# Digital_DSP.net
KiCad netlist of a schematic drawn in Altium Designer
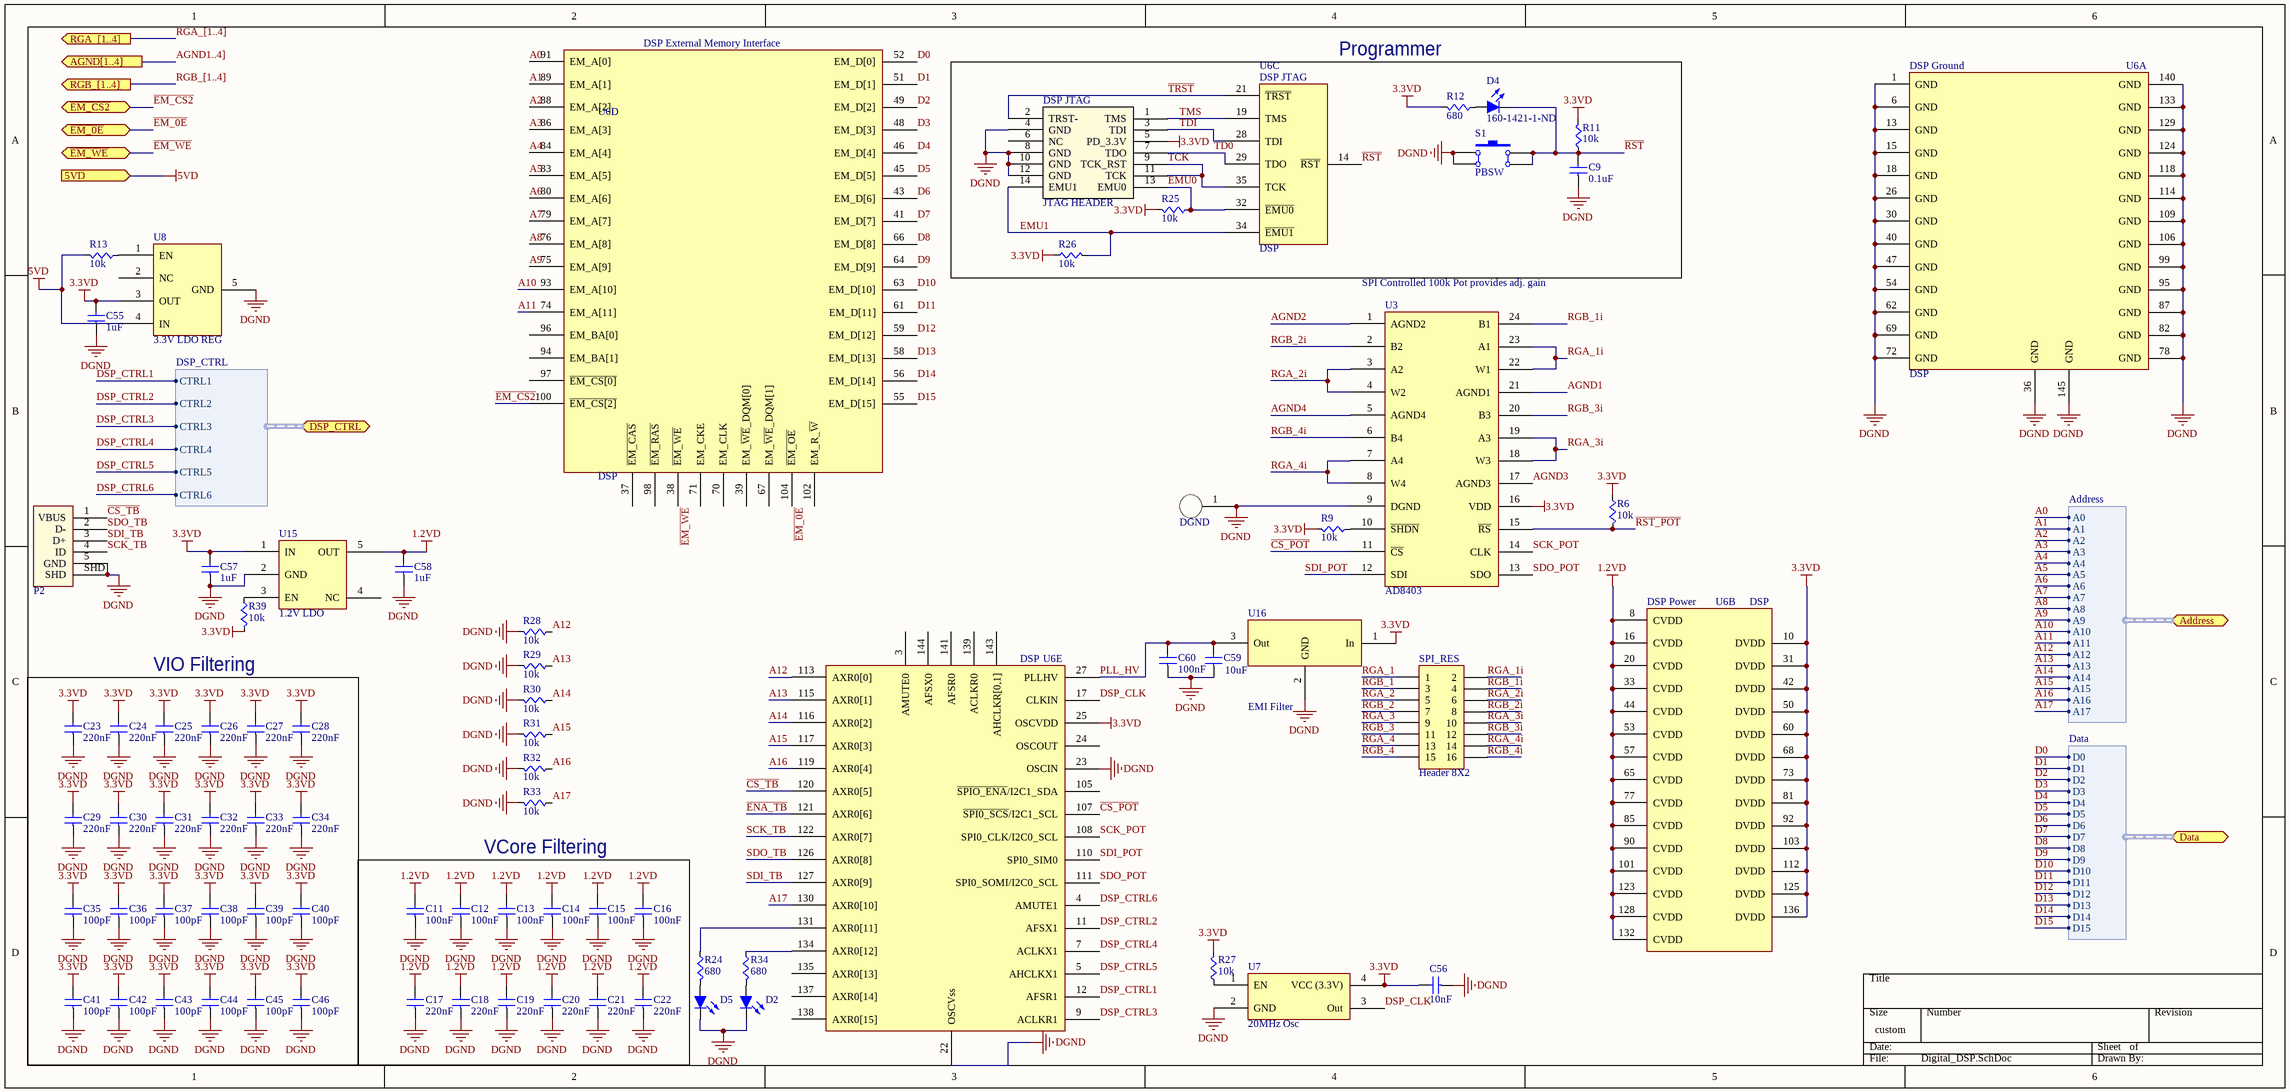
[diagram p0: Digital_DSP.SchDoc]

(export (version "E")
  (design (tool "Eeschema 10.0.6"))
  (components
    (comp (ref "C9")
      (value "0.1uF")
      (footprint "CAPC0603")
      (fields (field (name "Comment") "Cap"))
      (libsource (lib "SubjuGator8") (part "Cap"))
    )
    (comp (ref "C11")
      (value "100nF")
      (footprint "CAPC0603")
      (fields (field (name "Comment") "Cap"))
      (libsource (lib "SubjuGator8") (part "Cap"))
    )
    (comp (ref "C12")
      (value "100nF")
      (footprint "CAPC0603")
      (fields (field (name "Comment") "Cap"))
      (libsource (lib "SubjuGator8") (part "Cap"))
    )
    (comp (ref "C13")
      (value "100nF")
      (footprint "CAPC0603")
      (fields (field (name "Comment") "Cap"))
      (libsource (lib "SubjuGator8") (part "Cap"))
    )
    (comp (ref "C14")
      (value "100nF")
      (footprint "CAPC0603")
      (fields (field (name "Comment") "Cap"))
      (libsource (lib "SubjuGator8") (part "Cap"))
    )
    (comp (ref "C15")
      (value "100nF")
      (footprint "CAPC0603")
      (fields (field (name "Comment") "Cap"))
      (libsource (lib "SubjuGator8") (part "Cap"))
    )
    (comp (ref "C16")
      (value "100nF")
      (footprint "CAPC0603")
      (fields (field (name "Comment") "Cap"))
      (libsource (lib "SubjuGator8") (part "Cap"))
    )
    (comp (ref "C17")
      (value "220nF")
      (footprint "CAPC0603")
      (fields (field (name "Comment") "Cap"))
      (libsource (lib "SubjuGator8") (part "Cap"))
    )
    (comp (ref "C18")
      (value "220nF")
      (footprint "CAPC0603")
      (fields (field (name "Comment") "Cap"))
      (libsource (lib "SubjuGator8") (part "Cap"))
    )
    (comp (ref "C19")
      (value "220nF")
      (footprint "CAPC0603")
      (fields (field (name "Comment") "Cap"))
      (libsource (lib "SubjuGator8") (part "Cap"))
    )
    (comp (ref "C20")
      (value "220nF")
      (footprint "CAPC0603")
      (fields (field (name "Comment") "Cap"))
      (libsource (lib "SubjuGator8") (part "Cap"))
    )
    (comp (ref "C21")
      (value "220nF")
      (footprint "CAPC0603")
      (fields (field (name "Comment") "Cap"))
      (libsource (lib "SubjuGator8") (part "Cap"))
    )
    (comp (ref "C22")
      (value "220nF")
      (footprint "CAPC0603")
      (fields (field (name "Comment") "Cap"))
      (libsource (lib "SubjuGator8") (part "Cap"))
    )
    (comp (ref "C23")
      (value "220nF")
      (footprint "CAPC0603")
      (fields (field (name "Comment") "Cap"))
      (libsource (lib "SubjuGator8") (part "Cap"))
    )
    (comp (ref "C24")
      (value "220nF")
      (footprint "CAPC0603")
      (fields (field (name "Comment") "Cap"))
      (libsource (lib "SubjuGator8") (part "Cap"))
    )
    (comp (ref "C25")
      (value "220nF")
      (footprint "CAPC0603")
      (fields (field (name "Comment") "Cap"))
      (libsource (lib "SubjuGator8") (part "Cap"))
    )
    (comp (ref "C26")
      (value "220nF")
      (footprint "CAPC0603")
      (fields (field (name "Comment") "Cap"))
      (libsource (lib "SubjuGator8") (part "Cap"))
    )
    (comp (ref "C27")
      (value "220nF")
      (footprint "CAPC0603")
      (fields (field (name "Comment") "Cap"))
      (libsource (lib "SubjuGator8") (part "Cap"))
    )
    (comp (ref "C28")
      (value "220nF")
      (footprint "CAPC0603")
      (fields (field (name "Comment") "Cap"))
      (libsource (lib "SubjuGator8") (part "Cap"))
    )
    (comp (ref "C29")
      (value "220nF")
      (footprint "CAPC0603")
      (fields (field (name "Comment") "Cap"))
      (libsource (lib "SubjuGator8") (part "Cap"))
    )
    (comp (ref "C30")
      (value "220nF")
      (footprint "CAPC0603")
      (fields (field (name "Comment") "Cap"))
      (libsource (lib "SubjuGator8") (part "Cap"))
    )
    (comp (ref "C31")
      (value "220nF")
      (footprint "CAPC0603")
      (fields (field (name "Comment") "Cap"))
      (libsource (lib "SubjuGator8") (part "Cap"))
    )
    (comp (ref "C32")
      (value "220nF")
      (footprint "CAPC0603")
      (fields (field (name "Comment") "Cap"))
      (libsource (lib "SubjuGator8") (part "Cap"))
    )
    (comp (ref "C33")
      (value "220nF")
      (footprint "CAPC0603")
      (fields (field (name "Comment") "Cap"))
      (libsource (lib "SubjuGator8") (part "Cap"))
    )
    (comp (ref "C34")
      (value "220nF")
      (footprint "CAPC0603")
      (fields (field (name "Comment") "Cap"))
      (libsource (lib "SubjuGator8") (part "Cap"))
    )
    (comp (ref "C35")
      (value "100pF")
      (footprint "CAPC0603")
      (fields (field (name "Comment") "Cap"))
      (libsource (lib "SubjuGator8") (part "Cap"))
    )
    (comp (ref "C36")
      (value "100pF")
      (footprint "CAPC0603")
      (fields (field (name "Comment") "Cap"))
      (libsource (lib "SubjuGator8") (part "Cap"))
    )
    (comp (ref "C37")
      (value "100pF")
      (footprint "CAPC0603")
      (fields (field (name "Comment") "Cap"))
      (libsource (lib "SubjuGator8") (part "Cap"))
    )
    (comp (ref "C38")
      (value "100pF")
      (footprint "CAPC0603")
      (fields (field (name "Comment") "Cap"))
      (libsource (lib "SubjuGator8") (part "Cap"))
    )
    (comp (ref "C39")
      (value "100pF")
      (footprint "CAPC0603")
      (fields (field (name "Comment") "Cap"))
      (libsource (lib "SubjuGator8") (part "Cap"))
    )
    (comp (ref "C40")
      (value "100pF")
      (footprint "CAPC0603")
      (fields (field (name "Comment") "Cap"))
      (libsource (lib "SubjuGator8") (part "Cap"))
    )
    (comp (ref "C41")
      (value "100pF")
      (footprint "CAPC0603")
      (fields (field (name "Comment") "Cap"))
      (libsource (lib "SubjuGator8") (part "Cap"))
    )
    (comp (ref "C42")
      (value "100pF")
      (footprint "CAPC0603")
      (fields (field (name "Comment") "Cap"))
      (libsource (lib "SubjuGator8") (part "Cap"))
    )
    (comp (ref "C43")
      (value "100pF")
      (footprint "CAPC0603")
      (fields (field (name "Comment") "Cap"))
      (libsource (lib "SubjuGator8") (part "Cap"))
    )
    (comp (ref "C44")
      (value "100pF")
      (footprint "CAPC0603")
      (fields (field (name "Comment") "Cap"))
      (libsource (lib "SubjuGator8") (part "Cap"))
    )
    (comp (ref "C45")
      (value "100pF")
      (footprint "CAPC0603")
      (fields (field (name "Comment") "Cap"))
      (libsource (lib "SubjuGator8") (part "Cap"))
    )
    (comp (ref "C46")
      (value "100pF")
      (footprint "CAPC0603")
      (fields (field (name "Comment") "Cap"))
      (libsource (lib "SubjuGator8") (part "Cap"))
    )
    (comp (ref "C55")
      (value "1uF")
      (footprint "CAPC0603")
      (description "CAP CER 1UF 50V 10% X7R 1206")
      (fields (field (name "Comment") "Cap1206"))
      (libsource (lib "Passives") (part "Cap1206"))
    )
    (comp (ref "C56")
      (value "10nF")
      (footprint "CAPC0603")
      (fields (field (name "Comment") "Cap"))
      (libsource (lib "SubjuGator8") (part "Cap"))
    )
    (comp (ref "C57")
      (value "1uF")
      (footprint "CAPC0603")
      (description "CAP CER 1UF 50V 10% X7R 1206")
      (fields (field (name "Comment") "Cap1206"))
      (libsource (lib "Passives") (part "Cap1206"))
    )
    (comp (ref "C58")
      (value "1uF")
      (footprint "CAPC0603")
      (description "CAP CER 1UF 50V 10% X7R 1206")
      (fields (field (name "Comment") "Cap1206"))
      (libsource (lib "Passives") (part "Cap1206"))
    )
    (comp (ref "C59")
      (value "10uF")
      (footprint "CAP1210")
      (description "CAP CER 10UF 50V 20% X5R 1210")
      (fields (field (name "Comment") "CAP1210"))
      (libsource (lib "SubjuGator8") (part "CAP1210"))
    )
    (comp (ref "C60")
      (value "100nF")
      (footprint "CAPC0603")
      (fields (field (name "Comment") "Cap"))
      (libsource (lib "SubjuGator8") (part "Cap"))
    )
    (comp (ref "D2")
      (value "LED-RED")
      (footprint "Hydrophone:LED0805-RED")
      (description "Light Emitting Diode - RED")
      (fields
        (field (name "MANUFACTURER PART NUMBER") "LTST-C171CKT")
        (field (name "MANUFACTURER") "Lite-On Inc")
      )
      (libsource (lib "Hydrophone") (part "LED-RED"))
    )
    (comp (ref "D4")
      (value "LED-RED")
      (footprint "Hydrophone:LED0805-RED")
      (description "Light Emitting Diode - RED")
      (fields
        (field (name "MANUFACTURER PART NUMBER") "LTST-C171CKT")
        (field (name "MANUFACTURER") "Lite-On Inc")
        (field (name "SUPPLIER PART NUMBER") "160-1421-1-ND")
      )
      (libsource (lib "Hydrophone") (part "LED-RED"))
    )
    (comp (ref "D5")
      (value "LED-RED")
      (footprint "Hydrophone:LED0805-RED")
      (description "Light Emitting Diode - RED")
      (fields
        (field (name "MANUFACTURER PART NUMBER") "LTST-C171CKT")
        (field (name "MANUFACTURER") "Lite-On Inc")
      )
      (libsource (lib "Hydrophone") (part "LED-RED"))
    )
    (comp (ref "DGND")
      (value "Test_Point")
      (footprint "TP")
      (description "TEST POINT PC COMPACT .063\"D")
      (libsource (lib "Hydrophone") (part "Test_Point"))
    )
    (comp (ref "DSP JTAG")
      (value "JTAG HEADER")
      (footprint "Hydrophone:JTAG HEADER - 14")
      (description "14 Pin JTAG Header")
      (libsource (lib "Hydrophone") (part "JTAG-TI_14"))
    )
    (comp (ref "P2")
      (value "USB Micro")
      (footprint "10118192-0001LF")
      (description "USB Mini B Metal Shield SMT")
      (libsource (lib "SubjuGator8") (part "USB Micro"))
    )
    (comp (ref "R6")
      (value "10k")
      (footprint "RES0603")
      (fields (field (name "Comment") "Res"))
      (libsource (lib "SubjuGator8") (part "Res"))
    )
    (comp (ref "R9")
      (value "10k")
      (footprint "RES0603")
      (fields (field (name "Comment") "Res"))
      (libsource (lib "SubjuGator8") (part "Res"))
    )
    (comp (ref "R11")
      (value "10k")
      (footprint "RES0603")
      (fields (field (name "Comment") "Res"))
      (libsource (lib "Passives") (part "Res"))
    )
    (comp (ref "R12")
      (value "680")
      (footprint "RES0603")
      (fields (field (name "Comment") "Res"))
      (libsource (lib "SubjuGator8") (part "Res"))
    )
    (comp (ref "R13")
      (value "10k")
      (footprint "RES0603")
      (fields (field (name "Comment") "Res"))
      (libsource (lib "SubjuGator8") (part "Res"))
    )
    (comp (ref "R24")
      (value "680")
      (footprint "RES0603")
      (fields (field (name "Comment") "Res"))
      (libsource (lib "SubjuGator8") (part "Res"))
    )
    (comp (ref "R25")
      (value "10k")
      (footprint "RES0603")
      (fields (field (name "Comment") "Res"))
      (libsource (lib "SubjuGator8") (part "Res"))
    )
    (comp (ref "R26")
      (value "10k")
      (footprint "RES0603")
      (fields (field (name "Comment") "Res"))
      (libsource (lib "SubjuGator8") (part "Res"))
    )
    (comp (ref "R27")
      (value "10k")
      (footprint "RES0603")
      (fields (field (name "Comment") "Res"))
      (libsource (lib "SubjuGator8") (part "Res"))
    )
    (comp (ref "R28")
      (value "10k")
      (footprint "RES0603")
      (fields (field (name "Comment") "Res"))
      (libsource (lib "SubjuGator8") (part "Res"))
    )
    (comp (ref "R29")
      (value "10k")
      (footprint "RES0603")
      (fields (field (name "Comment") "Res"))
      (libsource (lib "SubjuGator8") (part "Res"))
    )
    (comp (ref "R30")
      (value "10k")
      (footprint "RES0603")
      (fields (field (name "Comment") "Res"))
      (libsource (lib "SubjuGator8") (part "Res"))
    )
    (comp (ref "R31")
      (value "10k")
      (footprint "RES0603")
      (fields (field (name "Comment") "Res"))
      (libsource (lib "SubjuGator8") (part "Res"))
    )
    (comp (ref "R32")
      (value "10k")
      (footprint "RES0603")
      (fields (field (name "Comment") "Res"))
      (libsource (lib "SubjuGator8") (part "Res"))
    )
    (comp (ref "R33")
      (value "10k")
      (footprint "RES0603")
      (fields (field (name "Comment") "Res"))
      (libsource (lib "SubjuGator8") (part "Res"))
    )
    (comp (ref "R34")
      (value "680")
      (footprint "RES0603")
      (fields (field (name "Comment") "Res"))
      (libsource (lib "SubjuGator8") (part "Res"))
    )
    (comp (ref "R39")
      (value "10k")
      (footprint "RES0603")
      (fields (field (name "Comment") "Res"))
      (libsource (lib "SubjuGator8") (part "Res"))
    )
    (comp (ref "S1")
      (value "PBSW")
      (footprint "Hydrophone:PBSW")
      (description "Push Button Switch")
      (fields
        (field (name "MANUFACTURER") "Panasonic Electronic Components")
        (field (name "MANUFACTURER PART NUMBER") "EVQ-9P105M")
        (field (name "PUBLISHER") "Altium Limited")
      )
      (libsource (lib "Hydrophone") (part "SW-PB"))
    )
    (comp (ref "SPI_RES")
      (value "Header 8X2")
      (footprint "HDR2X8")
      (description "Header, 8-Pin, Dual row")
      (fields (field (name "PUBLISHER") "Altium Limited"))
      (libsource (lib "Miscellaneous Connectors") (part "Header 8X2"))
    )
    (comp (ref "U3")
      (value "AD8403")
      (footprint "SOIC-24n")
      (description "IC POT DGTL 8BIT 100K 4CH 24SOIC")
      (libsource (lib "SubjuGator8") (part "AD8403"))
    )
    (comp (ref "U6")
      (value "DSP")
      (footprint "LQFP_EP-144")
      (description "IC FLOATING POINT DSP 144-HTQFP")
      (libsource (lib "ICs") (part "TMS320C6726B"))
    )
    (comp (ref "U7")
      (value "20MHz Osc")
      (footprint "4-SMD")
      (description "OSC XO 20.000MHZ HCMOS TTL SMD")
      (libsource (lib "SubjuGator8") (part "CB3LV-3C-20M0000"))
    )
    (comp (ref "U8")
      (value "3.3V LDO REG")
      (footprint "SOT223-8N")
      (description "IC REG LDO 3.3V 0.5A SOT223-5")
      (libsource (lib "SubjuGator8") (part "LP38691"))
    )
    (comp (ref "U15")
      (value "1.2V LDO")
      (footprint "sot23-5n")
      (description "IC REG LDO 1.2V 0.15A SOT23-5")
      (libsource (lib "SubjuGator8") (part "LP3990MF-1.2"))
    )
    (comp (ref "U16")
      (value "EMI Filter")
      (footprint "1812")
      (description "FILTER 3-TERM 12MHZ 300MA SMD")
      (libsource (lib "SubjuGator8") (part "ACF451832-333"))
    )
  )
  (nets
    (net (code "5") (name "/A0") (class "Default")
      (node (ref "U6") (pin "91") (pinfunction "EM_A[0]_91") (pintype "passive"))
    )
    (net (code "6") (name "/A1") (class "Default")
      (node (ref "U6") (pin "89") (pinfunction "EM_A[1]_89") (pintype "passive"))
    )
    (net (code "7") (name "/A2") (class "Default")
      (node (ref "U6") (pin "88") (pinfunction "EM_A[2]_88") (pintype "passive"))
    )
    (net (code "8") (name "/A3") (class "Default")
      (node (ref "U6") (pin "86") (pinfunction "EM_A[3]_86") (pintype "passive"))
    )
    (net (code "9") (name "/A4") (class "Default")
      (node (ref "U6") (pin "84") (pinfunction "EM_A[4]_84") (pintype "passive"))
    )
    (net (code "10") (name "/A5") (class "Default")
      (node (ref "U6") (pin "83") (pinfunction "EM_A[5]_83") (pintype "passive"))
    )
    (net (code "11") (name "/A6") (class "Default")
      (node (ref "U6") (pin "80") (pinfunction "EM_A[6]_80") (pintype "passive"))
    )
    (net (code "12") (name "/A7") (class "Default")
      (node (ref "U6") (pin "79") (pinfunction "EM_A[7]_79") (pintype "passive"))
    )
    (net (code "13") (name "/A8") (class "Default")
      (node (ref "U6") (pin "76") (pinfunction "EM_A[8]_76") (pintype "passive"))
    )
    (net (code "14") (name "/A9") (class "Default")
      (node (ref "U6") (pin "75") (pinfunction "EM_A[9]_75") (pintype "passive"))
    )
    (net (code "15") (name "/A10") (class "Default")
      (node (ref "U6") (pin "93") (pinfunction "EM_A[10]_93") (pintype "passive"))
    )
    (net (code "16") (name "/A11") (class "Default")
      (node (ref "U6") (pin "74") (pinfunction "EM_A[11]_74") (pintype "passive"))
    )
    (net (code "17") (name "/A12") (class "Default")
      (node (ref "R28") (pin "2") (pinfunction "B_2") (pintype "passive"))
      (node (ref "U6") (pin "113") (pinfunction "AXR0[0]_113") (pintype "passive"))
    )
    (net (code "18") (name "/A13") (class "Default")
      (node (ref "R29") (pin "2") (pinfunction "B_2") (pintype "passive"))
      (node (ref "U6") (pin "115") (pinfunction "AXR0[1]_115") (pintype "passive"))
    )
    (net (code "19") (name "/A14") (class "Default")
      (node (ref "R30") (pin "2") (pinfunction "B_2") (pintype "passive"))
      (node (ref "U6") (pin "116") (pinfunction "AXR0[2]_116") (pintype "passive"))
    )
    (net (code "20") (name "/A15") (class "Default")
      (node (ref "R31") (pin "2") (pinfunction "B_2") (pintype "passive"))
      (node (ref "U6") (pin "117") (pinfunction "AXR0[3]_117") (pintype "passive"))
    )
    (net (code "21") (name "/A16") (class "Default")
      (node (ref "R32") (pin "2") (pinfunction "B_2") (pintype "passive"))
      (node (ref "U6") (pin "119") (pinfunction "AXR0[4]_119") (pintype "passive"))
    )
    (net (code "22") (name "/A17") (class "Default")
      (node (ref "R33") (pin "2") (pinfunction "B_2") (pintype "passive"))
      (node (ref "U6") (pin "130") (pinfunction "AXR0[10]_130") (pintype "passive"))
    )
    (net (code "23") (name "/AGND1") (class "Default")
      (node (ref "U3") (pin "21") (pinfunction "AGND1_21") (pintype "passive"))
    )
    (net (code "24") (name "/AGND2") (class "Default")
      (node (ref "U3") (pin "1") (pinfunction "AGND2_1") (pintype "passive"))
    )
    (net (code "25") (name "/AGND3") (class "Default")
      (node (ref "U3") (pin "17") (pinfunction "AGND3_17") (pintype "passive"))
    )
    (net (code "26") (name "/AGND4") (class "Default")
      (node (ref "U3") (pin "5") (pinfunction "AGND4_5") (pintype "passive"))
    )
    (net (code "27") (name "/D0") (class "Default")
      (node (ref "U6") (pin "52") (pinfunction "EM_D[0]_52") (pintype "passive"))
    )
    (net (code "28") (name "/D1") (class "Default")
      (node (ref "U6") (pin "51") (pinfunction "EM_D[1]_51") (pintype "passive"))
    )
    (net (code "29") (name "/D2") (class "Default")
      (node (ref "U6") (pin "49") (pinfunction "EM_D[2]_49") (pintype "passive"))
    )
    (net (code "30") (name "/D3") (class "Default")
      (node (ref "U6") (pin "48") (pinfunction "EM_D[3]_48") (pintype "passive"))
    )
    (net (code "31") (name "/D4") (class "Default")
      (node (ref "U6") (pin "46") (pinfunction "EM_D[4]_46") (pintype "passive"))
    )
    (net (code "32") (name "/D5") (class "Default")
      (node (ref "U6") (pin "45") (pinfunction "EM_D[5]_45") (pintype "passive"))
    )
    (net (code "33") (name "/D6") (class "Default")
      (node (ref "U6") (pin "43") (pinfunction "EM_D[6]_43") (pintype "passive"))
    )
    (net (code "34") (name "/D7") (class "Default")
      (node (ref "U6") (pin "41") (pinfunction "EM_D[7]_41") (pintype "passive"))
    )
    (net (code "35") (name "/D8") (class "Default")
      (node (ref "U6") (pin "66") (pinfunction "EM_D[8]_66") (pintype "passive"))
    )
    (net (code "36") (name "/D9") (class "Default")
      (node (ref "U6") (pin "64") (pinfunction "EM_D[9]_64") (pintype "passive"))
    )
    (net (code "37") (name "/D10") (class "Default")
      (node (ref "U6") (pin "63") (pinfunction "EM_D[10]_63") (pintype "passive"))
    )
    (net (code "38") (name "/D11") (class "Default")
      (node (ref "U6") (pin "61") (pinfunction "EM_D[11]_61") (pintype "passive"))
    )
    (net (code "39") (name "/D12") (class "Default")
      (node (ref "U6") (pin "59") (pinfunction "EM_D[12]_59") (pintype "passive"))
    )
    (net (code "40") (name "/D13") (class "Default")
      (node (ref "U6") (pin "58") (pinfunction "EM_D[13]_58") (pintype "passive"))
    )
    (net (code "41") (name "/D14") (class "Default")
      (node (ref "U6") (pin "56") (pinfunction "EM_D[14]_56") (pintype "passive"))
    )
    (net (code "42") (name "/D15") (class "Default")
      (node (ref "U6") (pin "55") (pinfunction "EM_D[15]_55") (pintype "passive"))
    )
    (net (code "43") (name "/DSP_CLK") (class "Default")
      (node (ref "U6") (pin "17") (pinfunction "CLKIN_17") (pintype "passive"))
      (node (ref "U7") (pin "3") (pinfunction "Out_3") (pintype "passive"))
    )
    (net (code "44") (name "/DSP_CTRL1") (class "Default")
      (node (ref "U6") (pin "12") (pinfunction "AFSR1_12") (pintype "passive"))
    )
    (net (code "45") (name "/DSP_CTRL2") (class "Default")
      (node (ref "U6") (pin "11") (pinfunction "AFSX1_11") (pintype "passive"))
    )
    (net (code "46") (name "/DSP_CTRL3") (class "Default")
      (node (ref "U6") (pin "9") (pinfunction "ACLKR1_9") (pintype "passive"))
    )
    (net (code "47") (name "/DSP_CTRL4") (class "Default")
      (node (ref "U6") (pin "7") (pinfunction "ACLKX1_7") (pintype "passive"))
    )
    (net (code "48") (name "/DSP_CTRL5") (class "Default")
      (node (ref "U6") (pin "5") (pinfunction "AHCLKX1_5") (pintype "passive"))
    )
    (net (code "49") (name "/DSP_CTRL6") (class "Default")
      (node (ref "U6") (pin "4") (pinfunction "AMUTE1_4") (pintype "passive"))
    )
    (net (code "50") (name "/EMU0") (class "Default")
      (node (ref "DSP JTAG") (pin "13") (pinfunction "EMU0_13") (pintype "passive"))
      (node (ref "R25") (pin "2") (pinfunction "B_2") (pintype "passive"))
      (node (ref "U6") (pin "32") (pinfunction "~{EMU0}_32") (pintype "passive"))
    )
    (net (code "51") (name "/EMU1") (class "Default")
      (node (ref "DSP JTAG") (pin "14") (pinfunction "EMU1_14") (pintype "passive"))
      (node (ref "R26") (pin "1") (pinfunction "A_1") (pintype "passive"))
      (node (ref "U6") (pin "34") (pinfunction "~{EMU1}_34") (pintype "passive"))
    )
    (net (code "52") (name "/PLL_HV") (class "Default")
      (node (ref "C59") (pin "1") (pinfunction "A_1") (pintype "passive"))
      (node (ref "C60") (pin "1") (pinfunction "A_1") (pintype "passive"))
      (node (ref "U16") (pin "3") (pinfunction "Out_3") (pintype "passive"))
      (node (ref "U6") (pin "27") (pinfunction "PLLHV_27") (pintype "passive"))
    )
    (net (code "53") (name "/RGA_1") (class "Default")
      (node (ref "SPI_RES") (pin "1") (pinfunction "1_1") (pintype "passive"))
    )
    (net (code "54") (name "/RGA_1i") (class "Default")
      (node (ref "SPI_RES") (pin "2") (pinfunction "2_2") (pintype "passive"))
      (node (ref "U3") (pin "22") (pinfunction "W1_22") (pintype "passive"))
      (node (ref "U3") (pin "23") (pinfunction "A1_23") (pintype "passive"))
    )
    (net (code "55") (name "/RGA_2") (class "Default")
      (node (ref "SPI_RES") (pin "5") (pinfunction "5_5") (pintype "passive"))
    )
    (net (code "56") (name "/RGA_2i") (class "Default")
      (node (ref "SPI_RES") (pin "6") (pinfunction "6_6") (pintype "passive"))
      (node (ref "U3") (pin "3") (pinfunction "A2_3") (pintype "passive"))
      (node (ref "U3") (pin "4") (pinfunction "W2_4") (pintype "passive"))
    )
    (net (code "57") (name "/RGA_3") (class "Default")
      (node (ref "SPI_RES") (pin "9") (pinfunction "9_9") (pintype "passive"))
    )
    (net (code "58") (name "/RGA_3i") (class "Default")
      (node (ref "SPI_RES") (pin "10") (pinfunction "10_10") (pintype "passive"))
      (node (ref "U3") (pin "18") (pinfunction "W3_18") (pintype "passive"))
      (node (ref "U3") (pin "19") (pinfunction "A3_19") (pintype "passive"))
    )
    (net (code "59") (name "/RGA_4") (class "Default")
      (node (ref "SPI_RES") (pin "13") (pinfunction "13_13") (pintype "passive"))
    )
    (net (code "60") (name "/RGA_4i") (class "Default")
      (node (ref "SPI_RES") (pin "14") (pinfunction "14_14") (pintype "passive"))
      (node (ref "U3") (pin "7") (pinfunction "A4_7") (pintype "passive"))
      (node (ref "U3") (pin "8") (pinfunction "W4_8") (pintype "passive"))
    )
    (net (code "62") (name "/RGB_1") (class "Default")
      (node (ref "SPI_RES") (pin "3") (pinfunction "3_3") (pintype "passive"))
    )
    (net (code "63") (name "/RGB_1i") (class "Default")
      (node (ref "SPI_RES") (pin "4") (pinfunction "4_4") (pintype "passive"))
      (node (ref "U3") (pin "24") (pinfunction "B1_24") (pintype "passive"))
    )
    (net (code "64") (name "/RGB_2") (class "Default")
      (node (ref "SPI_RES") (pin "7") (pinfunction "7_7") (pintype "passive"))
    )
    (net (code "65") (name "/RGB_2i") (class "Default")
      (node (ref "SPI_RES") (pin "8") (pinfunction "8_8") (pintype "passive"))
      (node (ref "U3") (pin "2") (pinfunction "B2_2") (pintype "passive"))
    )
    (net (code "66") (name "/RGB_3") (class "Default")
      (node (ref "SPI_RES") (pin "11") (pinfunction "11_11") (pintype "passive"))
    )
    (net (code "67") (name "/RGB_3i") (class "Default")
      (node (ref "SPI_RES") (pin "12") (pinfunction "12_12") (pintype "passive"))
      (node (ref "U3") (pin "20") (pinfunction "B3_20") (pintype "passive"))
    )
    (net (code "68") (name "/RGB_4") (class "Default")
      (node (ref "SPI_RES") (pin "15") (pinfunction "15_15") (pintype "passive"))
    )
    (net (code "69") (name "/RGB_4i") (class "Default")
      (node (ref "SPI_RES") (pin "16") (pinfunction "16_16") (pintype "passive"))
      (node (ref "U3") (pin "6") (pinfunction "B4_6") (pintype "passive"))
    )
    (net (code "71") (name "/SCK_POT") (class "Default")
      (node (ref "U3") (pin "14") (pinfunction "CLK_14") (pintype "passive"))
      (node (ref "U6") (pin "108") (pinfunction "SPI0_CLK/I2C0_SCL_108") (pintype "passive"))
    )
    (net (code "72") (name "/SCK_TB") (class "Default")
      (node (ref "P2") (pin "4") (pinfunction "ID_4") (pintype "passive"))
      (node (ref "U6") (pin "122") (pinfunction "AXR0[7]_122") (pintype "passive"))
    )
    (net (code "73") (name "/SDI_POT") (class "Default")
      (node (ref "U3") (pin "12") (pinfunction "SDI_12") (pintype "passive"))
      (node (ref "U6") (pin "110") (pinfunction "SPI0_SIM0_110") (pintype "passive"))
    )
    (net (code "74") (name "/SDI_TB") (class "Default")
      (node (ref "P2") (pin "3") (pinfunction "D+_3") (pintype "passive"))
      (node (ref "U6") (pin "127") (pinfunction "AXR0[9]_127") (pintype "passive"))
    )
    (net (code "75") (name "/SDO_POT") (class "Default")
      (node (ref "U3") (pin "13") (pinfunction "SDO_13") (pintype "passive"))
      (node (ref "U6") (pin "111") (pinfunction "SPI0_SOMI/I2C0_SCL_111") (pintype "passive"))
    )
    (net (code "76") (name "/SDO_TB") (class "Default")
      (node (ref "P2") (pin "2") (pinfunction "D-_2") (pintype "passive"))
      (node (ref "U6") (pin "126") (pinfunction "AXR0[8]_126") (pintype "passive"))
    )
    (net (code "77") (name "/TCK") (class "Default")
      (node (ref "DSP JTAG") (pin "11") (pinfunction "TCK_11") (pintype "passive"))
      (node (ref "DSP JTAG") (pin "9") (pinfunction "TCK_RST_9") (pintype "passive"))
      (node (ref "U6") (pin "35") (pinfunction "TCK_35") (pintype "passive"))
    )
    (net (code "78") (name "/TD0") (class "Default")
      (node (ref "DSP JTAG") (pin "7") (pinfunction "TDO_7") (pintype "passive"))
      (node (ref "U6") (pin "29") (pinfunction "TDO_29") (pintype "passive"))
    )
    (net (code "79") (name "/TDI") (class "Default")
      (node (ref "DSP JTAG") (pin "3") (pinfunction "TDI_3") (pintype "passive"))
      (node (ref "U6") (pin "28") (pinfunction "TDI_28") (pintype "passive"))
    )
    (net (code "80") (name "/TMS") (class "Default")
      (node (ref "DSP JTAG") (pin "1") (pinfunction "TMS_1") (pintype "passive"))
      (node (ref "U6") (pin "19") (pinfunction "TMS_19") (pintype "passive"))
    )
    (net (code "85") (name "/~{CS_POT}") (class "Default")
      (node (ref "U3") (pin "11") (pinfunction "~{CS}_11") (pintype "passive"))
      (node (ref "U6") (pin "107") (pinfunction "~{SPI0_SCS}/I2C1_SCL_107") (pintype "passive"))
    )
    (net (code "86") (name "/~{CS_TB}") (class "Default")
      (node (ref "P2") (pin "1") (pinfunction "VBUS_1") (pintype "passive"))
      (node (ref "U6") (pin "120") (pinfunction "AXR0[5]_120") (pintype "passive"))
    )
    (net (code "87") (name "/~{EM_0E}") (class "Default")
      (node (ref "U6") (pin "104") (pinfunction "~{EM_OE}_104") (pintype "passive"))
    )
    (net (code "88") (name "/~{EM_CS2}") (class "Default")
      (node (ref "U6") (pin "100") (pinfunction "~{EM_CS[2]}_100") (pintype "passive"))
    )
    (net (code "89") (name "/~{EM_WE}") (class "Default")
      (node (ref "U6") (pin "38") (pinfunction "~{EM_WE}_38") (pintype "passive"))
    )
    (net (code "90") (name "/~{ENA_TB}") (class "Default")
      (node (ref "U6") (pin "121") (pinfunction "AXR0[6]_121") (pintype "passive"))
    )
    (net (code "91") (name "/~{RST_POT}") (class "Default")
      (node (ref "R6") (pin "1") (pinfunction "A_1") (pintype "passive"))
      (node (ref "U3") (pin "15") (pinfunction "~{RS}_15") (pintype "passive"))
    )
    (net (code "92") (name "/~{RST}") (class "Default")
      (node (ref "C9") (pin "1") (pinfunction "A_1") (pintype "passive"))
      (node (ref "D4") (pin "1") (pinfunction "K_1") (pintype "passive"))
      (node (ref "R11") (pin "2") (pinfunction "B_2") (pintype "passive"))
      (node (ref "S1") (pin "3") (pinfunction "B_3") (pintype "passive"))
      (node (ref "S1") (pin "4") (pinfunction "B'_4") (pintype "passive"))
      (node (ref "U6") (pin "14") (pinfunction "~{RST}_14") (pintype "passive"))
    )
    (net (code "93") (name "/~{TRST}") (class "Default")
      (node (ref "DSP JTAG") (pin "2") (pinfunction "TRST-_2") (pintype "passive"))
      (node (ref "U6") (pin "21") (pinfunction "~{TRST}_21") (pintype "passive"))
    )
    (net (code "94") (name "1.2VD") (class "Default")
      (node (ref "C11") (pin "1") (pinfunction "A_1") (pintype "passive"))
      (node (ref "C12") (pin "1") (pinfunction "A_1") (pintype "passive"))
      (node (ref "C13") (pin "1") (pinfunction "A_1") (pintype "passive"))
      (node (ref "C14") (pin "1") (pinfunction "A_1") (pintype "passive"))
      (node (ref "C15") (pin "1") (pinfunction "A_1") (pintype "passive"))
      (node (ref "C16") (pin "1") (pinfunction "A_1") (pintype "passive"))
      (node (ref "C17") (pin "1") (pinfunction "A_1") (pintype "passive"))
      (node (ref "C18") (pin "1") (pinfunction "A_1") (pintype "passive"))
      (node (ref "C19") (pin "1") (pinfunction "A_1") (pintype "passive"))
      (node (ref "C20") (pin "1") (pinfunction "A_1") (pintype "passive"))
      (node (ref "C21") (pin "1") (pinfunction "A_1") (pintype "passive"))
      (node (ref "C22") (pin "1") (pinfunction "A_1") (pintype "passive"))
      (node (ref "C58") (pin "1") (pinfunction "A_1") (pintype "passive"))
      (node (ref "U15") (pin "5") (pinfunction "OUT_5") (pintype "passive"))
      (node (ref "U6") (pin "101") (pinfunction "CVDD_101") (pintype "passive"))
      (node (ref "U6") (pin "123") (pinfunction "CVDD_123") (pintype "passive"))
      (node (ref "U6") (pin "128") (pinfunction "CVDD_128") (pintype "passive"))
      (node (ref "U6") (pin "132") (pinfunction "CVDD_132") (pintype "passive"))
      (node (ref "U6") (pin "16") (pinfunction "CVDD_16") (pintype "passive"))
      (node (ref "U6") (pin "20") (pinfunction "CVDD_20") (pintype "passive"))
      (node (ref "U6") (pin "33") (pinfunction "CVDD_33") (pintype "passive"))
      (node (ref "U6") (pin "44") (pinfunction "CVDD_44") (pintype "passive"))
      (node (ref "U6") (pin "53") (pinfunction "CVDD_53") (pintype "passive"))
      (node (ref "U6") (pin "57") (pinfunction "CVDD_57") (pintype "passive"))
      (node (ref "U6") (pin "65") (pinfunction "CVDD_65") (pintype "passive"))
      (node (ref "U6") (pin "77") (pinfunction "CVDD_77") (pintype "passive"))
      (node (ref "U6") (pin "8") (pinfunction "CVDD_8") (pintype "passive"))
      (node (ref "U6") (pin "85") (pinfunction "CVDD_85") (pintype "passive"))
      (node (ref "U6") (pin "90") (pinfunction "CVDD_90") (pintype "passive"))
    )
    (net (code "95") (name "3.3VD") (class "Default")
      (node (ref "C23") (pin "1") (pinfunction "A_1") (pintype "passive"))
      (node (ref "C24") (pin "1") (pinfunction "A_1") (pintype "passive"))
      (node (ref "C25") (pin "1") (pinfunction "A_1") (pintype "passive"))
      (node (ref "C26") (pin "1") (pinfunction "A_1") (pintype "passive"))
      (node (ref "C27") (pin "1") (pinfunction "A_1") (pintype "passive"))
      (node (ref "C28") (pin "1") (pinfunction "A_1") (pintype "passive"))
      (node (ref "C29") (pin "1") (pinfunction "A_1") (pintype "passive"))
      (node (ref "C30") (pin "1") (pinfunction "A_1") (pintype "passive"))
      (node (ref "C31") (pin "1") (pinfunction "A_1") (pintype "passive"))
      (node (ref "C32") (pin "1") (pinfunction "A_1") (pintype "passive"))
      (node (ref "C33") (pin "1") (pinfunction "A_1") (pintype "passive"))
      (node (ref "C34") (pin "1") (pinfunction "A_1") (pintype "passive"))
      (node (ref "C35") (pin "1") (pinfunction "A_1") (pintype "passive"))
      (node (ref "C36") (pin "1") (pinfunction "A_1") (pintype "passive"))
      (node (ref "C37") (pin "1") (pinfunction "A_1") (pintype "passive"))
      (node (ref "C38") (pin "1") (pinfunction "A_1") (pintype "passive"))
      (node (ref "C39") (pin "1") (pinfunction "A_1") (pintype "passive"))
      (node (ref "C40") (pin "1") (pinfunction "A_1") (pintype "passive"))
      (node (ref "C41") (pin "1") (pinfunction "A_1") (pintype "passive"))
      (node (ref "C42") (pin "1") (pinfunction "A_1") (pintype "passive"))
      (node (ref "C43") (pin "1") (pinfunction "A_1") (pintype "passive"))
      (node (ref "C44") (pin "1") (pinfunction "A_1") (pintype "passive"))
      (node (ref "C45") (pin "1") (pinfunction "A_1") (pintype "passive"))
      (node (ref "C46") (pin "1") (pinfunction "A_1") (pintype "passive"))
      (node (ref "C55") (pin "1") (pinfunction "A_1") (pintype "passive"))
      (node (ref "C56") (pin "1") (pinfunction "A_1") (pintype "passive"))
      (node (ref "C57") (pin "1") (pinfunction "A_1") (pintype "passive"))
      (node (ref "DSP JTAG") (pin "5") (pinfunction "PD_3.3V_5") (pintype "passive"))
      (node (ref "R11") (pin "1") (pinfunction "A_1") (pintype "passive"))
      (node (ref "R12") (pin "1") (pinfunction "A_1") (pintype "passive"))
      (node (ref "R25") (pin "1") (pinfunction "A_1") (pintype "passive"))
      (node (ref "R26") (pin "2") (pinfunction "B_2") (pintype "passive"))
      (node (ref "R27") (pin "1") (pinfunction "A_1") (pintype "passive"))
      (node (ref "R39") (pin "1") (pinfunction "A_1") (pintype "passive"))
      (node (ref "R6") (pin "2") (pinfunction "B_2") (pintype "passive"))
      (node (ref "R9") (pin "1") (pinfunction "A_1") (pintype "passive"))
      (node (ref "U15") (pin "1") (pinfunction "IN_1") (pintype "passive"))
      (node (ref "U16") (pin "1") (pinfunction "In_1") (pintype "passive"))
      (node (ref "U3") (pin "16") (pinfunction "VDD_16") (pintype "passive"))
      (node (ref "U6") (pin "10") (pinfunction "DVDD_10") (pintype "passive"))
      (node (ref "U6") (pin "103") (pinfunction "DVDD_103") (pintype "passive"))
      (node (ref "U6") (pin "112") (pinfunction "DVDD_112") (pintype "passive"))
      (node (ref "U6") (pin "125") (pinfunction "DVDD_125") (pintype "passive"))
      (node (ref "U6") (pin "136") (pinfunction "DVDD_136") (pintype "passive"))
      (node (ref "U6") (pin "25") (pinfunction "OSCVDD_25") (pintype "passive"))
      (node (ref "U6") (pin "31") (pinfunction "DVDD_31") (pintype "passive"))
      (node (ref "U6") (pin "42") (pinfunction "DVDD_42") (pintype "passive"))
      (node (ref "U6") (pin "50") (pinfunction "DVDD_50") (pintype "passive"))
      (node (ref "U6") (pin "60") (pinfunction "DVDD_60") (pintype "passive"))
      (node (ref "U6") (pin "68") (pinfunction "DVDD_68") (pintype "passive"))
      (node (ref "U6") (pin "73") (pinfunction "DVDD_73") (pintype "passive"))
      (node (ref "U6") (pin "81") (pinfunction "DVDD_81") (pintype "passive"))
      (node (ref "U6") (pin "92") (pinfunction "DVDD_92") (pintype "passive"))
      (node (ref "U7") (pin "4") (pinfunction "VCC_(3.3V)_4") (pintype "passive"))
      (node (ref "U8") (pin "3") (pinfunction "OUT_3") (pintype "passive"))
    )
    (net (code "96") (name "5VD") (class "Default")
      (node (ref "R13") (pin "1") (pinfunction "A_1") (pintype "passive"))
      (node (ref "U8") (pin "4") (pinfunction "IN_4") (pintype "passive"))
    )
    (net (code "97") (name "DGND") (class "Default")
      (node (ref "C11") (pin "2") (pinfunction "B_2") (pintype "passive"))
      (node (ref "C12") (pin "2") (pinfunction "B_2") (pintype "passive"))
      (node (ref "C13") (pin "2") (pinfunction "B_2") (pintype "passive"))
      (node (ref "C14") (pin "2") (pinfunction "B_2") (pintype "passive"))
      (node (ref "C15") (pin "2") (pinfunction "B_2") (pintype "passive"))
      (node (ref "C16") (pin "2") (pinfunction "B_2") (pintype "passive"))
      (node (ref "C17") (pin "2") (pinfunction "B_2") (pintype "passive"))
      (node (ref "C18") (pin "2") (pinfunction "B_2") (pintype "passive"))
      (node (ref "C19") (pin "2") (pinfunction "B_2") (pintype "passive"))
      (node (ref "C20") (pin "2") (pinfunction "B_2") (pintype "passive"))
      (node (ref "C21") (pin "2") (pinfunction "B_2") (pintype "passive"))
      (node (ref "C22") (pin "2") (pinfunction "B_2") (pintype "passive"))
      (node (ref "C23") (pin "2") (pinfunction "B_2") (pintype "passive"))
      (node (ref "C24") (pin "2") (pinfunction "B_2") (pintype "passive"))
      (node (ref "C25") (pin "2") (pinfunction "B_2") (pintype "passive"))
      (node (ref "C26") (pin "2") (pinfunction "B_2") (pintype "passive"))
      (node (ref "C27") (pin "2") (pinfunction "B_2") (pintype "passive"))
      (node (ref "C28") (pin "2") (pinfunction "B_2") (pintype "passive"))
      (node (ref "C29") (pin "2") (pinfunction "B_2") (pintype "passive"))
      (node (ref "C30") (pin "2") (pinfunction "B_2") (pintype "passive"))
      (node (ref "C31") (pin "2") (pinfunction "B_2") (pintype "passive"))
      (node (ref "C32") (pin "2") (pinfunction "B_2") (pintype "passive"))
      (node (ref "C33") (pin "2") (pinfunction "B_2") (pintype "passive"))
      (node (ref "C34") (pin "2") (pinfunction "B_2") (pintype "passive"))
      (node (ref "C35") (pin "2") (pinfunction "B_2") (pintype "passive"))
      (node (ref "C36") (pin "2") (pinfunction "B_2") (pintype "passive"))
      (node (ref "C37") (pin "2") (pinfunction "B_2") (pintype "passive"))
      (node (ref "C38") (pin "2") (pinfunction "B_2") (pintype "passive"))
      (node (ref "C39") (pin "2") (pinfunction "B_2") (pintype "passive"))
      (node (ref "C40") (pin "2") (pinfunction "B_2") (pintype "passive"))
      (node (ref "C41") (pin "2") (pinfunction "B_2") (pintype "passive"))
      (node (ref "C42") (pin "2") (pinfunction "B_2") (pintype "passive"))
      (node (ref "C43") (pin "2") (pinfunction "B_2") (pintype "passive"))
      (node (ref "C44") (pin "2") (pinfunction "B_2") (pintype "passive"))
      (node (ref "C45") (pin "2") (pinfunction "B_2") (pintype "passive"))
      (node (ref "C46") (pin "2") (pinfunction "B_2") (pintype "passive"))
      (node (ref "C55") (pin "2") (pinfunction "B_2") (pintype "passive"))
      (node (ref "C56") (pin "2") (pinfunction "B_2") (pintype "passive"))
      (node (ref "C57") (pin "2") (pinfunction "B_2") (pintype "passive"))
      (node (ref "C58") (pin "2") (pinfunction "B_2") (pintype "passive"))
      (node (ref "C59") (pin "2") (pinfunction "B_2") (pintype "passive"))
      (node (ref "C60") (pin "2") (pinfunction "B_2") (pintype "passive"))
      (node (ref "C9") (pin "2") (pinfunction "B_2") (pintype "passive"))
      (node (ref "D2") (pin "1") (pinfunction "K_1") (pintype "passive"))
      (node (ref "D5") (pin "1") (pinfunction "K_1") (pintype "passive"))
      (node (ref "DGND") (pin "1") (pintype "passive"))
      (node (ref "DSP JTAG") (pin "10") (pinfunction "GND_10") (pintype "passive"))
      (node (ref "DSP JTAG") (pin "12") (pinfunction "GND_12") (pintype "passive"))
      (node (ref "DSP JTAG") (pin "4") (pinfunction "GND_4") (pintype "passive"))
      (node (ref "DSP JTAG") (pin "8") (pinfunction "GND_8") (pintype "passive"))
      (node (ref "P2") (pin "5") (pinfunction "GND_5") (pintype "passive"))
      (node (ref "P2") (pin "SHD") (pinfunction "SHD_SHD") (pintype "passive"))
      (node (ref "R28") (pin "1") (pinfunction "A_1") (pintype "passive"))
      (node (ref "R29") (pin "1") (pinfunction "A_1") (pintype "passive"))
      (node (ref "R30") (pin "1") (pinfunction "A_1") (pintype "passive"))
      (node (ref "R31") (pin "1") (pinfunction "A_1") (pintype "passive"))
      (node (ref "R32") (pin "1") (pinfunction "A_1") (pintype "passive"))
      (node (ref "R33") (pin "1") (pinfunction "A_1") (pintype "passive"))
      (node (ref "S1") (pin "1") (pinfunction "A_1") (pintype "passive"))
      (node (ref "S1") (pin "2") (pinfunction "A'_2") (pintype "passive"))
      (node (ref "U15") (pin "2") (pinfunction "GND_2") (pintype "passive"))
      (node (ref "U16") (pin "2") (pinfunction "GND_2") (pintype "passive"))
      (node (ref "U3") (pin "9") (pinfunction "DGND_9") (pintype "passive"))
      (node (ref "U6") (pin "1") (pinfunction "GND_1") (pintype "passive"))
      (node (ref "U6") (pin "106") (pinfunction "GND_106") (pintype "passive"))
      (node (ref "U6") (pin "109") (pinfunction "GND_109") (pintype "passive"))
      (node (ref "U6") (pin "114") (pinfunction "GND_114") (pintype "passive"))
      (node (ref "U6") (pin "118") (pinfunction "GND_118") (pintype "passive"))
      (node (ref "U6") (pin "124") (pinfunction "GND_124") (pintype "passive"))
      (node (ref "U6") (pin "129") (pinfunction "GND_129") (pintype "passive"))
      (node (ref "U6") (pin "13") (pinfunction "GND_13") (pintype "passive"))
      (node (ref "U6") (pin "133") (pinfunction "GND_133") (pintype "passive"))
      (node (ref "U6") (pin "140") (pinfunction "GND_140") (pintype "passive"))
      (node (ref "U6") (pin "145") (pinfunction "GND_145") (pintype "passive"))
      (node (ref "U6") (pin "15") (pinfunction "GND_15") (pintype "passive"))
      (node (ref "U6") (pin "18") (pinfunction "GND_18") (pintype "passive"))
      (node (ref "U6") (pin "22") (pinfunction "OSCVss_22") (pintype "passive"))
      (node (ref "U6") (pin "23") (pinfunction "OSCIN_23") (pintype "passive"))
      (node (ref "U6") (pin "26") (pinfunction "GND_26") (pintype "passive"))
      (node (ref "U6") (pin "30") (pinfunction "GND_30") (pintype "passive"))
      (node (ref "U6") (pin "36") (pinfunction "GND_36") (pintype "passive"))
      (node (ref "U6") (pin "40") (pinfunction "GND_40") (pintype "passive"))
      (node (ref "U6") (pin "47") (pinfunction "GND_47") (pintype "passive"))
      (node (ref "U6") (pin "54") (pinfunction "GND_54") (pintype "passive"))
      (node (ref "U6") (pin "6") (pinfunction "GND_6") (pintype "passive"))
      (node (ref "U6") (pin "62") (pinfunction "GND_62") (pintype "passive"))
      (node (ref "U6") (pin "69") (pinfunction "GND_69") (pintype "passive"))
      (node (ref "U6") (pin "72") (pinfunction "GND_72") (pintype "passive"))
      (node (ref "U6") (pin "78") (pinfunction "GND_78") (pintype "passive"))
      (node (ref "U6") (pin "82") (pinfunction "GND_82") (pintype "passive"))
      (node (ref "U6") (pin "87") (pinfunction "GND_87") (pintype "passive"))
      (node (ref "U6") (pin "95") (pinfunction "GND_95") (pintype "passive"))
      (node (ref "U6") (pin "99") (pinfunction "GND_99") (pintype "passive"))
      (node (ref "U7") (pin "2") (pinfunction "GND_2") (pintype "passive"))
      (node (ref "U8") (pin "5") (pinfunction "GND_5") (pintype "passive"))
    )
    (net (code "98") (name "Net-(D2-A)") (class "Default")
      (node (ref "D2") (pin "2") (pinfunction "A_2") (pintype "passive"))
      (node (ref "R34") (pin "1") (pinfunction "A_1") (pintype "passive"))
    )
    (net (code "99") (name "Net-(D4-A)") (class "Default")
      (node (ref "D4") (pin "2") (pinfunction "A_2") (pintype "passive"))
      (node (ref "R12") (pin "2") (pinfunction "B_2") (pintype "passive"))
    )
    (net (code "100") (name "Net-(D5-A)") (class "Default")
      (node (ref "D5") (pin "2") (pinfunction "A_2") (pintype "passive"))
      (node (ref "R24") (pin "1") (pinfunction "A_1") (pintype "passive"))
    )
    (net (code "101") (name "Net-(R9-B)") (class "Default")
      (node (ref "R9") (pin "2") (pinfunction "B_2") (pintype "passive"))
      (node (ref "U3") (pin "10") (pinfunction "~{SHDN}_10") (pintype "passive"))
    )
    (net (code "102") (name "Net-(R13-B)") (class "Default")
      (node (ref "R13") (pin "2") (pinfunction "B_2") (pintype "passive"))
      (node (ref "U8") (pin "1") (pinfunction "EN_1") (pintype "passive"))
    )
    (net (code "103") (name "Net-(R24-B)") (class "Default")
      (node (ref "R24") (pin "2") (pinfunction "B_2") (pintype "passive"))
      (node (ref "U6") (pin "131") (pinfunction "AXR0[11]_131") (pintype "passive"))
    )
    (net (code "104") (name "Net-(R27-B)") (class "Default")
      (node (ref "R27") (pin "2") (pinfunction "B_2") (pintype "passive"))
      (node (ref "U7") (pin "1") (pinfunction "EN_1") (pintype "passive"))
    )
    (net (code "105") (name "Net-(R34-B)") (class "Default")
      (node (ref "R34") (pin "2") (pinfunction "B_2") (pintype "passive"))
      (node (ref "U6") (pin "134") (pinfunction "AXR0[12]_134") (pintype "passive"))
    )
    (net (code "106") (name "Net-(R39-B)") (class "Default")
      (node (ref "R39") (pin "2") (pinfunction "B_2") (pintype "passive"))
      (node (ref "U15") (pin "3") (pinfunction "EN_3") (pintype "passive"))
    )
    (net (code "107") (name "unconnected-(DSP JTAG-NC-Pad6)") (class "Default")
      (node (ref "DSP JTAG") (pin "6") (pinfunction "NC_6") (pintype "passive"))
    )
    (net (code "108") (name "unconnected-(U6D-EM_BA[0]-Pad96)") (class "Default")
      (node (ref "U6") (pin "96") (pinfunction "EM_BA[0]_96") (pintype "passive"))
    )
    (net (code "109") (name "unconnected-(U6D-EM_BA[1]-Pad94)") (class "Default")
      (node (ref "U6") (pin "94") (pinfunction "EM_BA[1]_94") (pintype "passive"))
    )
    (net (code "110") (name "unconnected-(U6D-EM_CKE-Pad71)") (class "Default")
      (node (ref "U6") (pin "71") (pinfunction "EM_CKE_71") (pintype "passive"))
    )
    (net (code "111") (name "unconnected-(U6D-EM_CLK-Pad70)") (class "Default")
      (node (ref "U6") (pin "70") (pinfunction "EM_CLK_70") (pintype "passive"))
    )
    (net (code "112") (name "unconnected-(U6D-EM_R_~{W}-Pad102)") (class "Default")
      (node (ref "U6") (pin "102") (pinfunction "EM_R_~{W}_102") (pintype "passive"))
    )
    (net (code "113") (name "unconnected-(U6D-EM_~{WE}_DQM[0]-Pad39)") (class "Default")
      (node (ref "U6") (pin "39") (pinfunction "EM_~{WE}_DQM[0]_39") (pintype "passive"))
    )
    (net (code "114") (name "unconnected-(U6D-EM_~{WE}_DQM[1]-Pad67)") (class "Default")
      (node (ref "U6") (pin "67") (pinfunction "EM_~{WE}_DQM[1]_67") (pintype "passive"))
    )
    (net (code "115") (name "unconnected-(U6D-~{EM_CAS}-Pad37)") (class "Default")
      (node (ref "U6") (pin "37") (pinfunction "~{EM_CAS}_37") (pintype "passive"))
    )
    (net (code "116") (name "unconnected-(U6D-~{EM_CS[0]}-Pad97)") (class "Default")
      (node (ref "U6") (pin "97") (pinfunction "~{EM_CS[0]}_97") (pintype "passive"))
    )
    (net (code "117") (name "unconnected-(U6D-~{EM_RAS}-Pad98)") (class "Default")
      (node (ref "U6") (pin "98") (pinfunction "~{EM_RAS}_98") (pintype "passive"))
    )
    (net (code "118") (name "unconnected-(U6E-ACLKR0-Pad139)") (class "Default")
      (node (ref "U6") (pin "139") (pinfunction "ACLKR0_139") (pintype "passive"))
    )
    (net (code "119") (name "unconnected-(U6E-AFSR0-Pad141)") (class "Default")
      (node (ref "U6") (pin "141") (pinfunction "AFSR0_141") (pintype "passive"))
    )
    (net (code "120") (name "unconnected-(U6E-AFSX0-Pad144)") (class "Default")
      (node (ref "U6") (pin "144") (pinfunction "AFSX0_144") (pintype "passive"))
    )
    (net (code "121") (name "unconnected-(U6E-AHCLKR[0,1]-Pad143)") (class "Default")
      (node (ref "U6") (pin "143") (pinfunction "AHCLKR[0,1]_143") (pintype "passive"))
    )
    (net (code "122") (name "unconnected-(U6E-AMUTE0-Pad3)") (class "Default")
      (node (ref "U6") (pin "3") (pinfunction "AMUTE0_3") (pintype "passive"))
    )
    (net (code "123") (name "unconnected-(U6E-AXR0[13]-Pad135)") (class "Default")
      (node (ref "U6") (pin "135") (pinfunction "AXR0[13]_135") (pintype "passive"))
    )
    (net (code "124") (name "unconnected-(U6E-AXR0[14]-Pad137)") (class "Default")
      (node (ref "U6") (pin "137") (pinfunction "AXR0[14]_137") (pintype "passive"))
    )
    (net (code "125") (name "unconnected-(U6E-AXR0[15]-Pad138)") (class "Default")
      (node (ref "U6") (pin "138") (pinfunction "AXR0[15]_138") (pintype "passive"))
    )
    (net (code "126") (name "unconnected-(U6E-OSCOUT-Pad24)") (class "Default")
      (node (ref "U6") (pin "24") (pinfunction "OSCOUT_24") (pintype "passive"))
    )
    (net (code "127") (name "unconnected-(U6E-~{SPIO_ENA}{slash}I2C1_SDA-Pad105)") (class "Default")
      (node (ref "U6") (pin "105") (pinfunction "~{SPIO_ENA}/I2C1_SDA_105") (pintype "passive"))
    )
    (net (code "128") (name "unconnected-(U8-NC-Pad2)") (class "Default")
      (node (ref "U8") (pin "2") (pinfunction "NC_2") (pintype "passive"))
    )
    (net (code "129") (name "unconnected-(U15-NC-Pad4)") (class "Default")
      (node (ref "U15") (pin "4") (pinfunction "NC_4") (pintype "passive"))
    )
  )
)
